# 3_INTERFACE_DOS_DRIVERS.net
KiCad netlist of a schematic drawn in Altium Designer
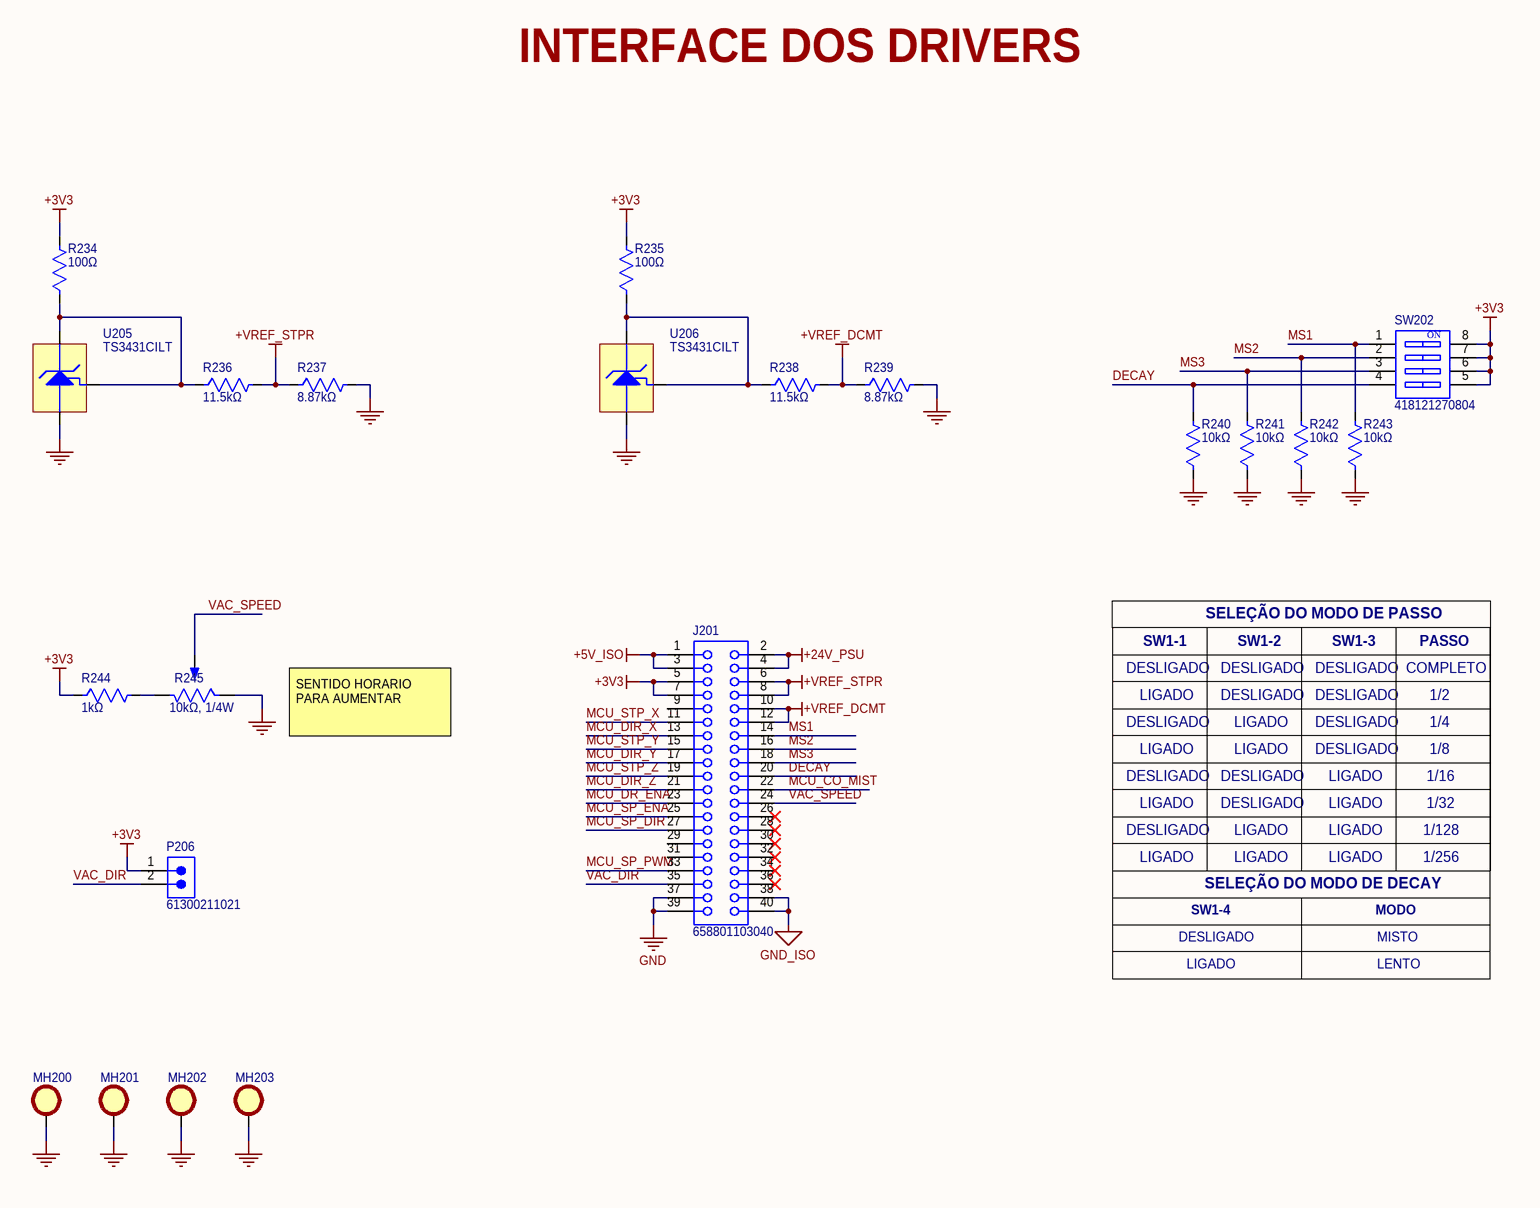
[diagram p0: 3_INTERFACE_DOS_DRIVERS.SchDoc]

(export (version "E")
  (design (tool "Eeschema 10.0.6"))
  (components
    (comp (ref "J201")
      (value "658801103040")
      (footprint "658801103040")
      (description "WR-BTB Board to Board Connector, Female Receptacle, height 11.75mm, pitch 0.8mm, 40p")
      (fields (field (name "MANUFACTURER") "Wurth Elektronik"))
      (libsource (lib "WE - Electromechanical Components") (part "Header_Female_2R_40P"))
    )
    (comp (ref "MH200")
      (value "Mounting Hole 2.5mm")
      (footprint "MOUNTING_HOLE_M2P5_PLATED")
      (description "PLATED MOUNTING HOLE WITH 2.5MM DIAMETER")
      (libsource (lib "Electro-Mechanical") (part "MTH-2P5MM-PLATED"))
    )
    (comp (ref "MH201")
      (value "Mounting Hole 2.5mm")
      (footprint "MOUNTING_HOLE_M2P5_PLATED")
      (description "PLATED MOUNTING HOLE WITH 2.5MM DIAMETER")
      (libsource (lib "Electro-Mechanical") (part "MTH-2P5MM-PLATED"))
    )
    (comp (ref "MH202")
      (value "Mounting Hole 2.5mm")
      (footprint "MOUNTING_HOLE_M2P5_PLATED")
      (description "PLATED MOUNTING HOLE WITH 2.5MM DIAMETER")
      (libsource (lib "Electro-Mechanical") (part "MTH-2P5MM-PLATED"))
    )
    (comp (ref "MH203")
      (value "Mounting Hole 2.5mm")
      (footprint "MOUNTING_HOLE_M2P5_PLATED")
      (description "PLATED MOUNTING HOLE WITH 2.5MM DIAMETER")
      (libsource (lib "Electro-Mechanical") (part "MTH-2P5MM-PLATED"))
    )
    (comp (ref "P206")
      (value "61300211021")
      (footprint "61300211021")
      (description "WR-PHD Pin Header, THT, Angled, pitch 2.54mm, 1 Row, 2P")
      (fields (field (name "MANUFACTURER") "Wurth Elektronik"))
      (libsource (lib "WE - Electromechanical Components") (part "Header_Male_1R_02P"))
    )
    (comp (ref "R234")
      (value "100Ω")
      (footprint "0603-WAVE")
      (description "RES 100 OHM 1% 1/10W 0603")
      (fields
        (field (name "MANUFACTURER PART NUMBER") "RC0603FR-07100RL")
        (field (name "MANUFACTURER") "Yageo Group")
      )
      (libsource (lib "Resistors-0603-E96-Yageo") (part "RC0603FR-07100RL"))
    )
    (comp (ref "R235")
      (value "100Ω")
      (footprint "0603-WAVE")
      (description "RES 100 OHM 1% 1/10W 0603")
      (fields
        (field (name "MANUFACTURER PART NUMBER") "RC0603FR-07100RL")
        (field (name "MANUFACTURER") "Yageo Group")
      )
      (libsource (lib "Resistors-0603-E96-Yageo") (part "RC0603FR-07100RL"))
    )
    (comp (ref "R236")
      (value "11.5kΩ")
      (footprint "0603-WAVE")
      (description "RES 11.5K OHM 1% 1/10W 0603")
      (fields
        (field (name "MANUFACTURER PART NUMBER") "RC0603FR-0711K5L")
        (field (name "MANUFACTURER") "Yageo Group")
      )
      (libsource (lib "Resistors-0603-E96-Yageo") (part "RC0603FR-0711K5L"))
    )
    (comp (ref "R237")
      (value "8.87kΩ")
      (footprint "0603-WAVE")
      (description "RES 8.87K OHM 1% 1/10W 0603")
      (fields
        (field (name "MANUFACTURER PART NUMBER") "RC0603FR-078K87L")
        (field (name "MANUFACTURER") "Yageo Group")
      )
      (libsource (lib "Resistors-0603-E96-Yageo") (part "RC0603FR-078K87L"))
    )
    (comp (ref "R238")
      (value "11.5kΩ")
      (footprint "0603-WAVE")
      (description "RES 11.5K OHM 1% 1/10W 0603")
      (fields
        (field (name "MANUFACTURER PART NUMBER") "RC0603FR-0711K5L")
        (field (name "MANUFACTURER") "Yageo Group")
      )
      (libsource (lib "Resistors-0603-E96-Yageo") (part "RC0603FR-0711K5L"))
    )
    (comp (ref "R239")
      (value "8.87kΩ")
      (footprint "0603-WAVE")
      (description "RES 8.87K OHM 1% 1/10W 0603")
      (fields
        (field (name "MANUFACTURER PART NUMBER") "RC0603FR-078K87L")
        (field (name "MANUFACTURER") "Yageo Group")
      )
      (libsource (lib "Resistors-0603-E96-Yageo") (part "RC0603FR-078K87L"))
    )
    (comp (ref "R240")
      (value "10kΩ")
      (footprint "0603-WAVE")
      (description "RES 10K OHM 1% 1/10W 0603")
      (fields
        (field (name "MANUFACTURER PART NUMBER") "RC0603FR-0710KL")
        (field (name "MANUFACTURER") "Yageo Group")
      )
      (libsource (lib "Resistors-0603-E96-Yageo") (part "RC0603FR-0710KL"))
    )
    (comp (ref "R241")
      (value "10kΩ")
      (footprint "0603-WAVE")
      (description "RES 10K OHM 1% 1/10W 0603")
      (fields
        (field (name "MANUFACTURER PART NUMBER") "RC0603FR-0710KL")
        (field (name "MANUFACTURER") "Yageo Group")
      )
      (libsource (lib "Resistors-0603-E96-Yageo") (part "RC0603FR-0710KL"))
    )
    (comp (ref "R242")
      (value "10kΩ")
      (footprint "0603-WAVE")
      (description "RES 10K OHM 1% 1/10W 0603")
      (fields
        (field (name "MANUFACTURER PART NUMBER") "RC0603FR-0710KL")
        (field (name "MANUFACTURER") "Yageo Group")
      )
      (libsource (lib "Resistors-0603-E96-Yageo") (part "RC0603FR-0710KL"))
    )
    (comp (ref "R243")
      (value "10kΩ")
      (footprint "0603-WAVE")
      (description "RES 10K OHM 1% 1/10W 0603")
      (fields
        (field (name "MANUFACTURER PART NUMBER") "RC0603FR-0710KL")
        (field (name "MANUFACTURER") "Yageo Group")
      )
      (libsource (lib "Resistors-0603-E96-Yageo") (part "RC0603FR-0710KL"))
    )
    (comp (ref "R244")
      (value "1kΩ")
      (footprint "0603-WAVE")
      (description "RES 1K OHM 1% 1/10W 0603")
      (fields
        (field (name "MANUFACTURER PART NUMBER") "RC0603FR-071KL")
        (field (name "MANUFACTURER") "Yageo Group")
      )
      (libsource (lib "Resistors-0603-E96-Yageo") (part "RC0603FR-071KL"))
    )
    (comp (ref "R245")
      (value "10kΩ, 1/4W")
      (footprint "TRIM-3224W")
      (description "TRIMMER 10K OHM 0.25W J LEAD TOP")
      (fields (field (name "MANUFACTURER") "Bourns") (field (name "MANUFACTURER PART NUMBER") "3224W-1-103G"))
      (libsource (lib "Potentiometers") (part "3224W-1-103G"))
    )
    (comp (ref "SW202")
      (value "418121270804")
      (footprint "418121270804")
      (description "WS-DISV Small Compact SMT Dip Switch, Raised Actuator, pitch 2.54mm, 4p")
      (fields (field (name "MANUFACTURER") "Wurth Elektronik"))
      (libsource (lib "WE - Electromechanical Components") (part "DIP-4"))
    )
    (comp (ref "U205")
      (value "TS3431CILT")
      (footprint "SOT-23-3")
      (description "IC VREF SHUNT ADJ 0.25% SOT23-3")
      (fields (field (name "MANUFACTURER") "STMicroelectronics") (field (name "TOLERANCE") "0.25%"))
      (libsource (lib "Voltage-Reference") (part "TS3431CILT"))
    )
    (comp (ref "U206")
      (value "TS3431CILT")
      (footprint "SOT-23-3")
      (description "IC VREF SHUNT ADJ 0.25% SOT23-3")
      (fields (field (name "MANUFACTURER") "STMicroelectronics") (field (name "TOLERANCE") "0.25%"))
      (libsource (lib "Voltage-Reference") (part "TS3431CILT"))
    )
  )
  (nets
    (net (code "1") (name "+3V3") (class "Default")
      (node (ref "J201") (pin "5") (pinfunction "5_5") (pintype "passive"))
      (node (ref "J201") (pin "7") (pinfunction "7_7") (pintype "passive"))
      (node (ref "P206") (pin "1") (pinfunction "1_1") (pintype "passive"))
      (node (ref "R234") (pin "2") (pinfunction "2_2") (pintype "passive"))
      (node (ref "R235") (pin "2") (pinfunction "2_2") (pintype "passive"))
      (node (ref "R244") (pin "1") (pinfunction "1_1") (pintype "passive"))
      (node (ref "SW202") (pin "5") (pinfunction "5_5") (pintype "passive"))
      (node (ref "SW202") (pin "6") (pinfunction "6_6") (pintype "passive"))
      (node (ref "SW202") (pin "7") (pinfunction "7_7") (pintype "passive"))
      (node (ref "SW202") (pin "8") (pinfunction "8_8") (pintype "passive"))
    )
    (net (code "2") (name "+5V_ISO") (class "Default")
      (node (ref "J201") (pin "1") (pinfunction "1_1") (pintype "passive"))
      (node (ref "J201") (pin "3") (pinfunction "3_3") (pintype "passive"))
    )
    (net (code "3") (name "+24V_PSU") (class "Default")
      (node (ref "J201") (pin "2") (pinfunction "2_2") (pintype "passive"))
      (node (ref "J201") (pin "4") (pinfunction "4_4") (pintype "passive"))
    )
    (net (code "4") (name "+VREF_DCMT") (class "Default")
      (node (ref "J201") (pin "10") (pinfunction "10_10") (pintype "passive"))
      (node (ref "J201") (pin "12") (pinfunction "12_12") (pintype "passive"))
      (node (ref "R238") (pin "2") (pinfunction "2_2") (pintype "passive"))
      (node (ref "R239") (pin "1") (pinfunction "1_1") (pintype "passive"))
    )
    (net (code "5") (name "+VREF_STPR") (class "Default")
      (node (ref "J201") (pin "6") (pinfunction "6_6") (pintype "passive"))
      (node (ref "J201") (pin "8") (pinfunction "8_8") (pintype "passive"))
      (node (ref "R236") (pin "2") (pinfunction "2_2") (pintype "passive"))
      (node (ref "R237") (pin "1") (pinfunction "1_1") (pintype "passive"))
    )
    (net (code "6") (name "/DECAY") (class "Default")
      (node (ref "J201") (pin "20") (pinfunction "20_20") (pintype "passive"))
      (node (ref "R240") (pin "2") (pinfunction "2_2") (pintype "passive"))
      (node (ref "SW202") (pin "4") (pinfunction "4_4") (pintype "passive"))
    )
    (net (code "7") (name "/MCU_CO_MIST") (class "Default")
      (node (ref "J201") (pin "22") (pinfunction "22_22") (pintype "passive"))
    )
    (net (code "8") (name "/MCU_DIR_X") (class "Default")
      (node (ref "J201") (pin "13") (pinfunction "13_13") (pintype "passive"))
    )
    (net (code "9") (name "/MCU_DIR_Y") (class "Default")
      (node (ref "J201") (pin "17") (pinfunction "17_17") (pintype "passive"))
    )
    (net (code "10") (name "/MCU_DIR_Z") (class "Default")
      (node (ref "J201") (pin "21") (pinfunction "21_21") (pintype "passive"))
    )
    (net (code "11") (name "/MCU_DR_ENA") (class "Default")
      (node (ref "J201") (pin "23") (pinfunction "23_23") (pintype "passive"))
    )
    (net (code "12") (name "/MCU_SP_DIR") (class "Default")
      (node (ref "J201") (pin "27") (pinfunction "27_27") (pintype "passive"))
    )
    (net (code "13") (name "/MCU_SP_ENA") (class "Default")
      (node (ref "J201") (pin "25") (pinfunction "25_25") (pintype "passive"))
    )
    (net (code "14") (name "/MCU_SP_PWM") (class "Default")
      (node (ref "J201") (pin "33") (pinfunction "33_33") (pintype "passive"))
    )
    (net (code "15") (name "/MCU_STP_X") (class "Default")
      (node (ref "J201") (pin "11") (pinfunction "11_11") (pintype "passive"))
    )
    (net (code "16") (name "/MCU_STP_Y") (class "Default")
      (node (ref "J201") (pin "15") (pinfunction "15_15") (pintype "passive"))
    )
    (net (code "17") (name "/MCU_STP_Z") (class "Default")
      (node (ref "J201") (pin "19") (pinfunction "19_19") (pintype "passive"))
    )
    (net (code "18") (name "/MS1") (class "Default")
      (node (ref "J201") (pin "14") (pinfunction "14_14") (pintype "passive"))
      (node (ref "R243") (pin "2") (pinfunction "2_2") (pintype "passive"))
      (node (ref "SW202") (pin "1") (pinfunction "1_1") (pintype "passive"))
    )
    (net (code "19") (name "/MS2") (class "Default")
      (node (ref "J201") (pin "16") (pinfunction "16_16") (pintype "passive"))
      (node (ref "R242") (pin "2") (pinfunction "2_2") (pintype "passive"))
      (node (ref "SW202") (pin "2") (pinfunction "2_2") (pintype "passive"))
    )
    (net (code "20") (name "/MS3") (class "Default")
      (node (ref "J201") (pin "18") (pinfunction "18_18") (pintype "passive"))
      (node (ref "R241") (pin "2") (pinfunction "2_2") (pintype "passive"))
      (node (ref "SW202") (pin "3") (pinfunction "3_3") (pintype "passive"))
    )
    (net (code "21") (name "/VAC_DIR") (class "Default")
      (node (ref "J201") (pin "35") (pinfunction "35_35") (pintype "passive"))
      (node (ref "P206") (pin "2") (pinfunction "2_2") (pintype "passive"))
    )
    (net (code "22") (name "/VAC_SPEED") (class "Default")
      (node (ref "J201") (pin "24") (pinfunction "24_24") (pintype "passive"))
      (node (ref "R245") (pin "2") (pinfunction "WIPER_2") (pintype "passive"))
    )
    (net (code "23") (name "GND") (class "Default")
      (node (ref "J201") (pin "37") (pinfunction "37_37") (pintype "passive"))
      (node (ref "J201") (pin "39") (pinfunction "39_39") (pintype "passive"))
      (node (ref "MH200") (pin "H") (pinfunction "1_H") (pintype "passive"))
      (node (ref "MH201") (pin "H") (pinfunction "1_H") (pintype "passive"))
      (node (ref "MH202") (pin "H") (pinfunction "1_H") (pintype "passive"))
      (node (ref "MH203") (pin "H") (pinfunction "1_H") (pintype "passive"))
      (node (ref "R237") (pin "2") (pinfunction "2_2") (pintype "passive"))
      (node (ref "R239") (pin "2") (pinfunction "2_2") (pintype "passive"))
      (node (ref "R240") (pin "1") (pinfunction "1_1") (pintype "passive"))
      (node (ref "R241") (pin "1") (pinfunction "1_1") (pintype "passive"))
      (node (ref "R242") (pin "1") (pinfunction "1_1") (pintype "passive"))
      (node (ref "R243") (pin "1") (pinfunction "1_1") (pintype "passive"))
      (node (ref "R245") (pin "1") (pinfunction "CCW_1") (pintype "passive"))
      (node (ref "U205") (pin "3") (pinfunction "ANODE_3") (pintype "passive"))
      (node (ref "U206") (pin "3") (pinfunction "ANODE_3") (pintype "passive"))
    )
    (net (code "24") (name "GND_ISO") (class "Default")
      (node (ref "J201") (pin "38") (pinfunction "38_38") (pintype "passive"))
      (node (ref "J201") (pin "40") (pinfunction "40_40") (pintype "passive"))
    )
    (net (code "25") (name "Net-(R245-CW)") (class "Default")
      (node (ref "R244") (pin "2") (pinfunction "2_2") (pintype "passive"))
      (node (ref "R245") (pin "3") (pinfunction "CW_3") (pintype "passive"))
    )
    (net (code "26") (name "Net-(U205-CATHODE)") (class "Default")
      (node (ref "R234") (pin "1") (pinfunction "1_1") (pintype "passive"))
      (node (ref "R236") (pin "1") (pinfunction "1_1") (pintype "passive"))
      (node (ref "U205") (pin "1") (pinfunction "REF_1") (pintype "passive"))
      (node (ref "U205") (pin "2") (pinfunction "CATHODE_2") (pintype "passive"))
    )
    (net (code "27") (name "Net-(U206-CATHODE)") (class "Default")
      (node (ref "R235") (pin "1") (pinfunction "1_1") (pintype "passive"))
      (node (ref "R238") (pin "1") (pinfunction "1_1") (pintype "passive"))
      (node (ref "U206") (pin "1") (pinfunction "REF_1") (pintype "passive"))
      (node (ref "U206") (pin "2") (pinfunction "CATHODE_2") (pintype "passive"))
    )
    (net (code "28") (name "unconnected-(J201-Pad9)") (class "Default")
      (node (ref "J201") (pin "9") (pinfunction "9_9") (pintype "passive"))
    )
    (net (code "29") (name "unconnected-(J201-Pad26)") (class "Default")
      (node (ref "J201") (pin "26") (pinfunction "26_26") (pintype "passive+no_connect"))
    )
    (net (code "30") (name "unconnected-(J201-Pad28)") (class "Default")
      (node (ref "J201") (pin "28") (pinfunction "28_28") (pintype "passive+no_connect"))
    )
    (net (code "31") (name "unconnected-(J201-Pad29)") (class "Default")
      (node (ref "J201") (pin "29") (pinfunction "29_29") (pintype "passive"))
    )
    (net (code "32") (name "unconnected-(J201-Pad30)") (class "Default")
      (node (ref "J201") (pin "30") (pinfunction "30_30") (pintype "passive+no_connect"))
    )
    (net (code "33") (name "unconnected-(J201-Pad31)") (class "Default")
      (node (ref "J201") (pin "31") (pinfunction "31_31") (pintype "passive"))
    )
    (net (code "34") (name "unconnected-(J201-Pad32)") (class "Default")
      (node (ref "J201") (pin "32") (pinfunction "32_32") (pintype "passive+no_connect"))
    )
    (net (code "35") (name "unconnected-(J201-Pad34)") (class "Default")
      (node (ref "J201") (pin "34") (pinfunction "34_34") (pintype "passive+no_connect"))
    )
    (net (code "36") (name "unconnected-(J201-Pad36)") (class "Default")
      (node (ref "J201") (pin "36") (pinfunction "36_36") (pintype "passive+no_connect"))
    )
  )
)
